# rgb_led_driver.net
KiCad netlist of a schematic drawn in EAGLE
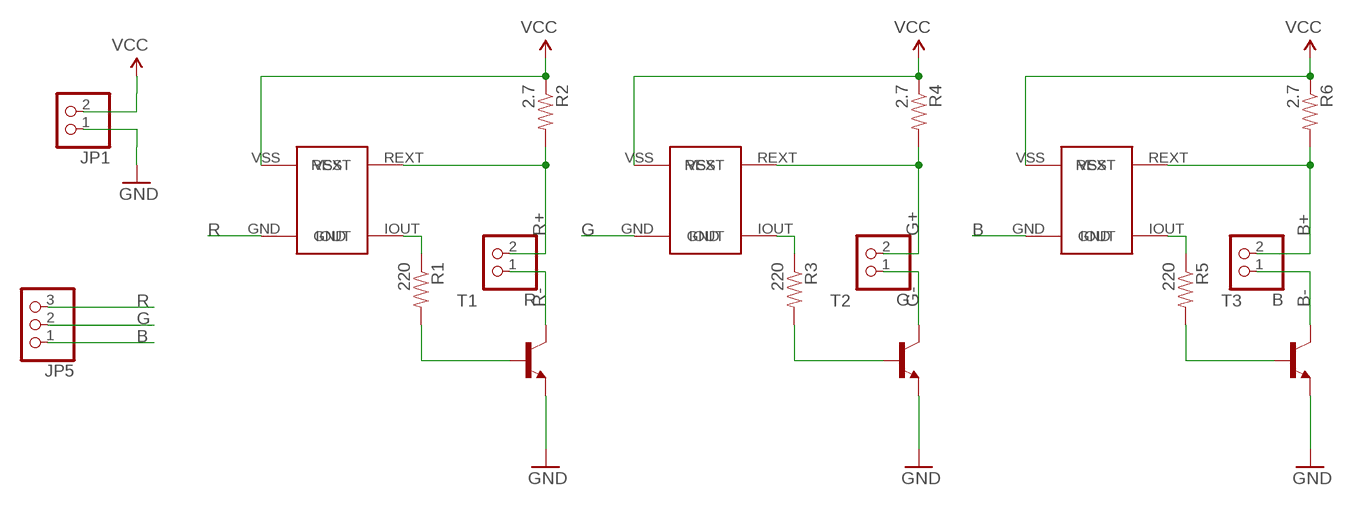
[diagram p0: schematic, sheet 1]

(export (version "E")
  (design (tool "Eeschema 10.0.6"))
  (components
    (comp (ref "B")
      (value "PINHD-1X2")
      (footprint "eagle-import:1X02")
      (libsource (lib "eagle-import") (part "PINHD-1X2"))
    )
    (comp (ref "G")
      (value "PINHD-1X2")
      (footprint "eagle-import:1X02")
      (libsource (lib "eagle-import") (part "PINHD-1X2"))
    )
    (comp (ref "JP1")
      (value "PINHD-1X2")
      (footprint "eagle-import:1X02")
      (libsource (lib "eagle-import") (part "PINHD-1X2"))
    )
    (comp (ref "JP5")
      (value "PINHD-1X3")
      (footprint "eagle-import:1X03")
      (libsource (lib "eagle-import") (part "PINHD-1X3"))
    )
    (comp (ref "R")
      (value "PINHD-1X2")
      (footprint "eagle-import:1X02")
      (libsource (lib "eagle-import") (part "PINHD-1X2"))
    )
    (comp (ref "R1")
      (value "220")
      (footprint "eagle-import:0805")
      (libsource (lib "eagle-import") (part "RESISTOR"))
    )
    (comp (ref "R2")
      (value "2.7")
      (footprint "eagle-import:AXIAL-0.3")
      (libsource (lib "eagle-import") (part "RESISTORPTH1"))
    )
    (comp (ref "R3")
      (value "220")
      (footprint "eagle-import:0805")
      (libsource (lib "eagle-import") (part "RESISTOR"))
    )
    (comp (ref "R4")
      (value "2.7")
      (footprint "eagle-import:AXIAL-0.3")
      (libsource (lib "eagle-import") (part "RESISTORPTH1"))
    )
    (comp (ref "R5")
      (value "220")
      (footprint "eagle-import:0805")
      (libsource (lib "eagle-import") (part "RESISTOR"))
    )
    (comp (ref "R6")
      (value "2.7")
      (footprint "eagle-import:AXIAL-0.3")
      (libsource (lib "eagle-import") (part "RESISTORPTH1"))
    )
    (comp (ref "T1")
      (value "-NPN-SOT89-BCE")
      (footprint "eagle-import:SOT89-BCE")
      (libsource (lib "eagle-import") (part "-NPN-SOT89-BCE"))
    )
    (comp (ref "T2")
      (value "-NPN-SOT89-BCE")
      (footprint "eagle-import:SOT89-BCE")
      (libsource (lib "eagle-import") (part "-NPN-SOT89-BCE"))
    )
    (comp (ref "T3")
      (value "-NPN-SOT89-BCE")
      (footprint "eagle-import:SOT89-BCE")
      (libsource (lib "eagle-import") (part "-NPN-SOT89-BCE"))
    )
    (comp (ref "U$1")
      (value "BCR401W")
      (footprint "eagle-import:SOT-343")
      (libsource (lib "eagle-import") (part "BCR401W"))
    )
    (comp (ref "U$2")
      (value "BCR401W")
      (footprint "eagle-import:SOT-343")
      (libsource (lib "eagle-import") (part "BCR401W"))
    )
    (comp (ref "U$9")
      (value "BCR401W")
      (footprint "eagle-import:SOT-343")
      (libsource (lib "eagle-import") (part "BCR401W"))
    )
  )
  (nets
    (net (code "1") (name "/B") (class "Default")
      (node (ref "JP5") (pin "1") (pinfunction "1_1") (pintype "passive"))
      (node (ref "U$2") (pin "GND") (pinfunction "GND_GND") (pintype "bidirectional"))
    )
    (net (code "2") (name "/B+") (class "Default")
      (node (ref "B") (pin "2") (pinfunction "2_2") (pintype "passive"))
      (node (ref "R6") (pin "P$2") (pinfunction "2_P$2") (pintype "passive"))
      (node (ref "U$2") (pin "REXT") (pinfunction "REXT_REXT") (pintype "bidirectional"))
    )
    (net (code "3") (name "/B-") (class "Default")
      (node (ref "B") (pin "1") (pinfunction "1_1") (pintype "passive"))
      (node (ref "T3") (pin "C") (pinfunction "C_C") (pintype "passive"))
    )
    (net (code "4") (name "/G") (class "Default")
      (node (ref "JP5") (pin "2") (pinfunction "2_2") (pintype "passive"))
      (node (ref "U$1") (pin "GND") (pinfunction "GND_GND") (pintype "bidirectional"))
    )
    (net (code "5") (name "/G+") (class "Default")
      (node (ref "G") (pin "2") (pinfunction "2_2") (pintype "passive"))
      (node (ref "R4") (pin "P$2") (pinfunction "2_P$2") (pintype "passive"))
      (node (ref "U$1") (pin "REXT") (pinfunction "REXT_REXT") (pintype "bidirectional"))
    )
    (net (code "6") (name "/G-") (class "Default")
      (node (ref "G") (pin "1") (pinfunction "1_1") (pintype "passive"))
      (node (ref "T2") (pin "C") (pinfunction "C_C") (pintype "passive"))
    )
    (net (code "7") (name "/R") (class "Default")
      (node (ref "JP5") (pin "3") (pinfunction "3_3") (pintype "passive"))
      (node (ref "U$9") (pin "GND") (pinfunction "GND_GND") (pintype "bidirectional"))
    )
    (net (code "8") (name "/R+") (class "Default")
      (node (ref "R") (pin "2") (pinfunction "2_2") (pintype "passive"))
      (node (ref "R2") (pin "P$2") (pinfunction "2_P$2") (pintype "passive"))
      (node (ref "U$9") (pin "REXT") (pinfunction "REXT_REXT") (pintype "bidirectional"))
    )
    (net (code "9") (name "/R-") (class "Default")
      (node (ref "R") (pin "1") (pinfunction "1_1") (pintype "passive"))
      (node (ref "T1") (pin "C") (pinfunction "C_C") (pintype "passive"))
    )
    (net (code "10") (name "GND") (class "Default")
      (node (ref "JP1") (pin "1") (pinfunction "1_1") (pintype "passive"))
      (node (ref "T1") (pin "E") (pinfunction "E_E") (pintype "passive"))
      (node (ref "T2") (pin "E") (pinfunction "E_E") (pintype "passive"))
      (node (ref "T3") (pin "E") (pinfunction "E_E") (pintype "passive"))
    )
    (net (code "11") (name "Net-(R1-Pad1)") (class "Default")
      (node (ref "R1") (pin "1") (pinfunction "1_1") (pintype "passive"))
      (node (ref "U$9") (pin "IOUT") (pinfunction "IOUT_IOUT") (pintype "bidirectional"))
    )
    (net (code "12") (name "Net-(R1-Pad2)") (class "Default")
      (node (ref "R1") (pin "2") (pinfunction "2_2") (pintype "passive"))
      (node (ref "T1") (pin "B") (pinfunction "B_B") (pintype "passive"))
    )
    (net (code "13") (name "Net-(R3-Pad1)") (class "Default")
      (node (ref "R3") (pin "1") (pinfunction "1_1") (pintype "passive"))
      (node (ref "U$1") (pin "IOUT") (pinfunction "IOUT_IOUT") (pintype "bidirectional"))
    )
    (net (code "14") (name "Net-(R3-Pad2)") (class "Default")
      (node (ref "R3") (pin "2") (pinfunction "2_2") (pintype "passive"))
      (node (ref "T2") (pin "B") (pinfunction "B_B") (pintype "passive"))
    )
    (net (code "15") (name "Net-(R5-Pad1)") (class "Default")
      (node (ref "R5") (pin "1") (pinfunction "1_1") (pintype "passive"))
      (node (ref "U$2") (pin "IOUT") (pinfunction "IOUT_IOUT") (pintype "bidirectional"))
    )
    (net (code "16") (name "Net-(R5-Pad2)") (class "Default")
      (node (ref "R5") (pin "2") (pinfunction "2_2") (pintype "passive"))
      (node (ref "T3") (pin "B") (pinfunction "B_B") (pintype "passive"))
    )
    (net (code "17") (name "VCC") (class "Default")
      (node (ref "JP1") (pin "2") (pinfunction "2_2") (pintype "passive"))
      (node (ref "R2") (pin "P$1") (pinfunction "1_P$1") (pintype "passive"))
      (node (ref "R4") (pin "P$1") (pinfunction "1_P$1") (pintype "passive"))
      (node (ref "R6") (pin "P$1") (pinfunction "1_P$1") (pintype "passive"))
      (node (ref "U$1") (pin "VSS") (pinfunction "VSS_VSS") (pintype "bidirectional"))
      (node (ref "U$2") (pin "VSS") (pinfunction "VSS_VSS") (pintype "bidirectional"))
      (node (ref "U$9") (pin "VSS") (pinfunction "VSS_VSS") (pintype "bidirectional"))
    )
  )
)
